# Nu_Multi.net
KiCad netlist of a schematic drawn in EAGLE
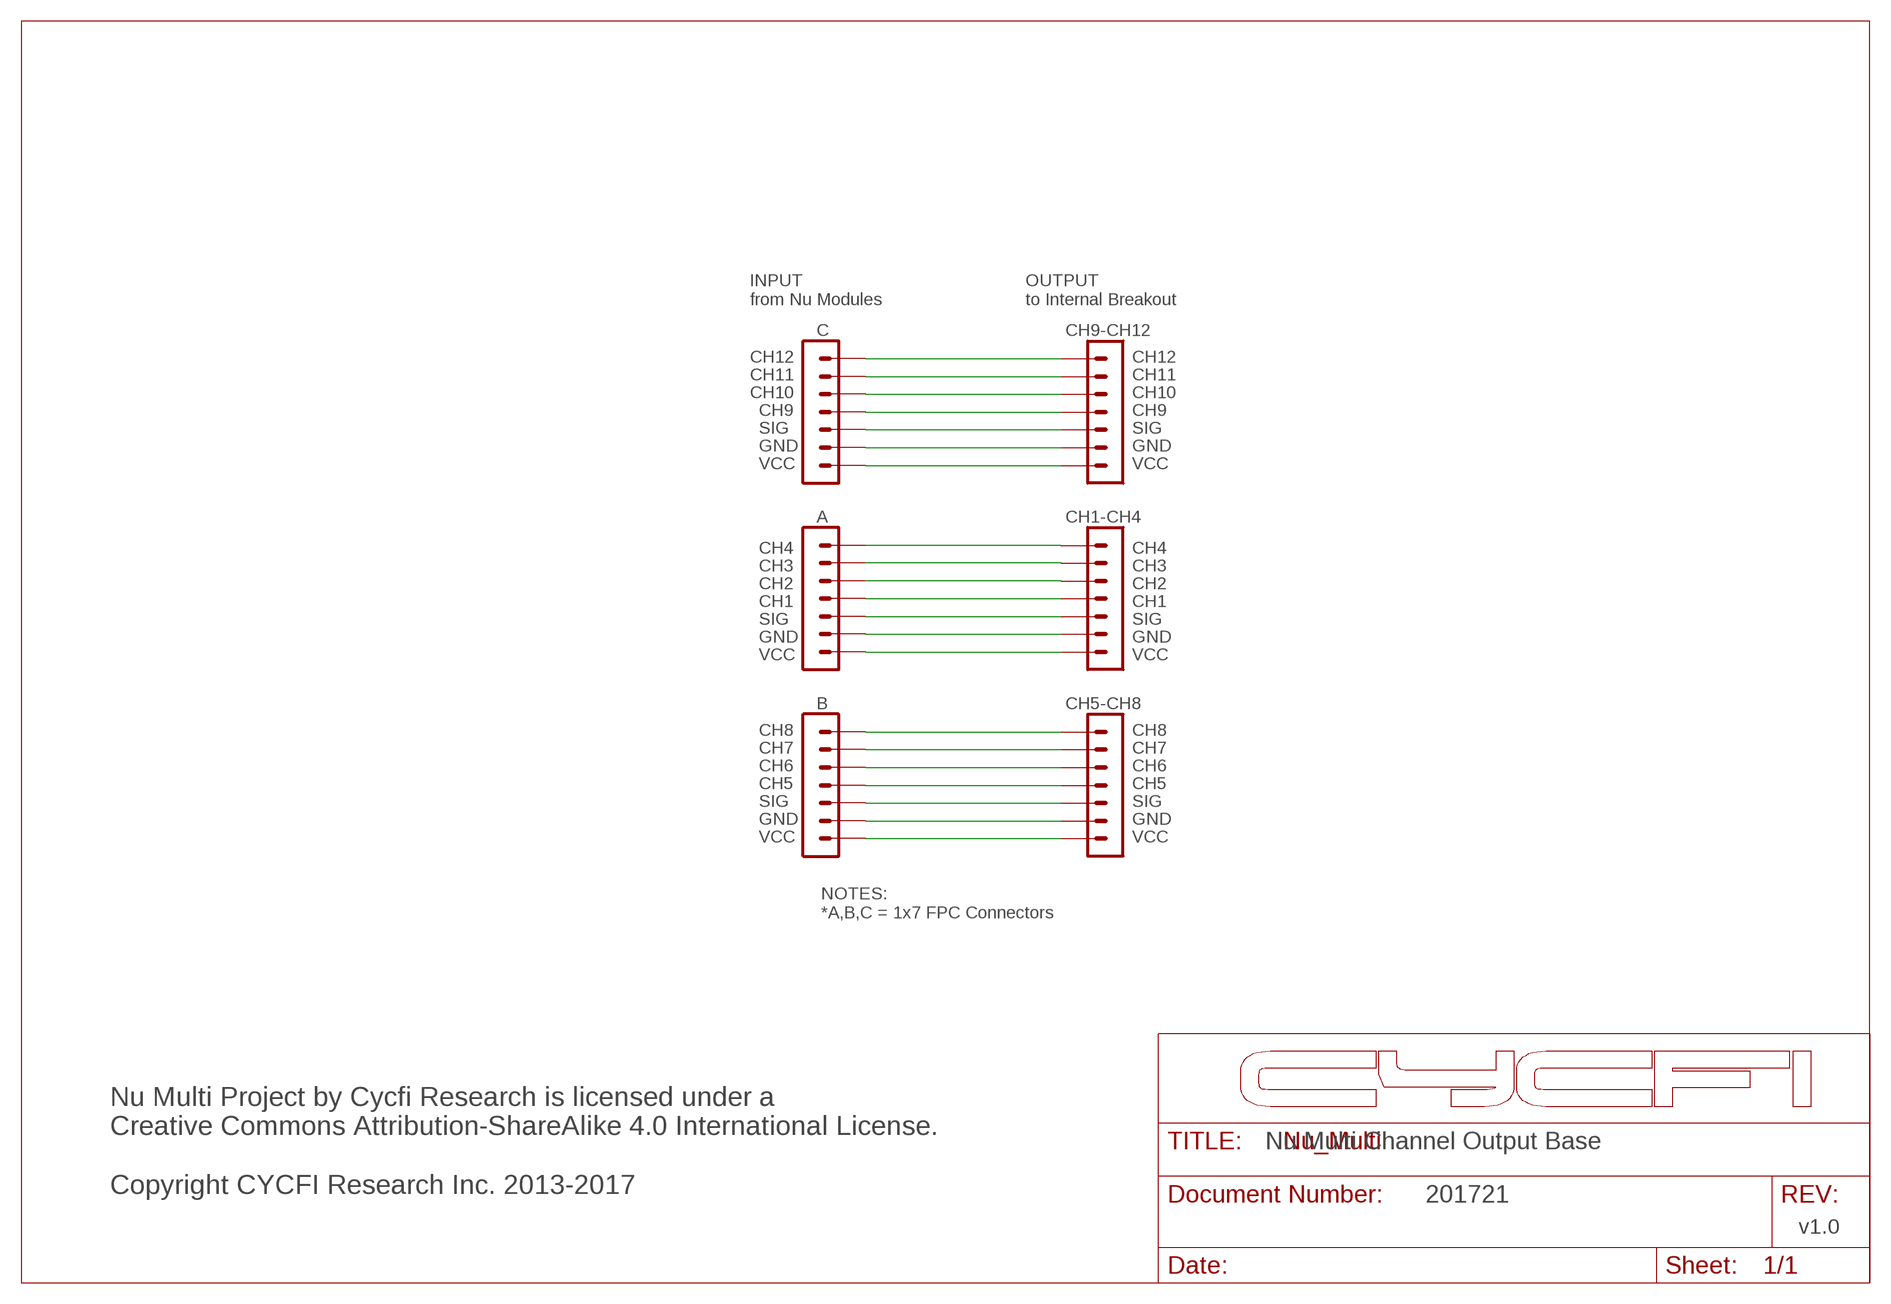
[diagram p0: schematic, sheet 1]

(export (version "E")
  (design (tool "Eeschema 10.0.6"))
  (components
    (comp (ref "H1")
      (value "7P_ZIF_59453-071110EDHLF")
      (footprint "eagle-import:7P_ZIF_59453-071110EDHLF")
      (libsource (lib "eagle-import") (part "7P_ZIF_59453-071110EDHLF"))
    )
    (comp (ref "H2")
      (value "7P_ZIF_59453-071110EDHLF")
      (footprint "eagle-import:7P_ZIF_59453-071110EDHLF")
      (libsource (lib "eagle-import") (part "7P_ZIF_59453-071110EDHLF"))
    )
    (comp (ref "H3")
      (value "7P_ZIF_59453-071110EDHLF")
      (footprint "eagle-import:7P_ZIF_59453-071110EDHLF")
      (libsource (lib "eagle-import") (part "7P_ZIF_59453-071110EDHLF"))
    )
    (comp (ref "H4")
      (value "7P_ZIF_59453-071110EDHLF")
      (footprint "eagle-import:7P_ZIF_59453-071110EDHLF")
      (libsource (lib "eagle-import") (part "7P_ZIF_59453-071110EDHLF"))
    )
    (comp (ref "H5")
      (value "7P_ZIF_59453-071110EDHLF")
      (footprint "eagle-import:7P_ZIF_59453-071110EDHLF")
      (libsource (lib "eagle-import") (part "7P_ZIF_59453-071110EDHLF"))
    )
    (comp (ref "H6")
      (value "7P_ZIF_59453-071110EDHLF")
      (footprint "eagle-import:7P_ZIF_59453-071110EDHLF")
      (libsource (lib "eagle-import") (part "7P_ZIF_59453-071110EDHLF"))
    )
  )
  (nets
    (net (code "1") (name "/GND") (class "Default")
      (node (ref "H1") (pin "P$6") (pinfunction "6_P$6") (pintype "passive"))
      (node (ref "H2") (pin "P$6") (pinfunction "6_P$6") (pintype "passive"))
      (node (ref "H3") (pin "P$6") (pinfunction "6_P$6") (pintype "passive"))
      (node (ref "H4") (pin "P$6") (pinfunction "6_P$6") (pintype "passive"))
      (node (ref "H5") (pin "P$6") (pinfunction "6_P$6") (pintype "passive"))
      (node (ref "H6") (pin "P$6") (pinfunction "6_P$6") (pintype "passive"))
    )
    (net (code "2") (name "Net-(H1-1)") (class "Default")
      (node (ref "H1") (pin "P$1") (pinfunction "1_P$1") (pintype "passive"))
      (node (ref "H3") (pin "P$1") (pinfunction "1_P$1") (pintype "passive"))
    )
    (net (code "3") (name "Net-(H1-2)") (class "Default")
      (node (ref "H1") (pin "P$2") (pinfunction "2_P$2") (pintype "passive"))
      (node (ref "H3") (pin "P$2") (pinfunction "2_P$2") (pintype "passive"))
    )
    (net (code "4") (name "Net-(H1-3)") (class "Default")
      (node (ref "H1") (pin "P$3") (pinfunction "3_P$3") (pintype "passive"))
      (node (ref "H3") (pin "P$3") (pinfunction "3_P$3") (pintype "passive"))
    )
    (net (code "5") (name "Net-(H1-4)") (class "Default")
      (node (ref "H1") (pin "P$4") (pinfunction "4_P$4") (pintype "passive"))
      (node (ref "H3") (pin "P$4") (pinfunction "4_P$4") (pintype "passive"))
    )
    (net (code "6") (name "Net-(H1-5)") (class "Default")
      (node (ref "H1") (pin "P$5") (pinfunction "5_P$5") (pintype "passive"))
      (node (ref "H3") (pin "P$5") (pinfunction "5_P$5") (pintype "passive"))
    )
    (net (code "7") (name "Net-(H1-7)") (class "Default")
      (node (ref "H1") (pin "P$7") (pinfunction "7_P$7") (pintype "passive"))
      (node (ref "H3") (pin "P$7") (pinfunction "7_P$7") (pintype "passive"))
    )
    (net (code "8") (name "Net-(H2-1)") (class "Default")
      (node (ref "H2") (pin "P$1") (pinfunction "1_P$1") (pintype "passive"))
      (node (ref "H4") (pin "P$1") (pinfunction "1_P$1") (pintype "passive"))
    )
    (net (code "9") (name "Net-(H2-2)") (class "Default")
      (node (ref "H2") (pin "P$2") (pinfunction "2_P$2") (pintype "passive"))
      (node (ref "H4") (pin "P$2") (pinfunction "2_P$2") (pintype "passive"))
    )
    (net (code "10") (name "Net-(H2-3)") (class "Default")
      (node (ref "H2") (pin "P$3") (pinfunction "3_P$3") (pintype "passive"))
      (node (ref "H4") (pin "P$3") (pinfunction "3_P$3") (pintype "passive"))
    )
    (net (code "11") (name "Net-(H2-4)") (class "Default")
      (node (ref "H2") (pin "P$4") (pinfunction "4_P$4") (pintype "passive"))
      (node (ref "H4") (pin "P$4") (pinfunction "4_P$4") (pintype "passive"))
    )
    (net (code "12") (name "Net-(H2-5)") (class "Default")
      (node (ref "H2") (pin "P$5") (pinfunction "5_P$5") (pintype "passive"))
      (node (ref "H4") (pin "P$5") (pinfunction "5_P$5") (pintype "passive"))
    )
    (net (code "13") (name "Net-(H2-7)") (class "Default")
      (node (ref "H2") (pin "P$7") (pinfunction "7_P$7") (pintype "passive"))
      (node (ref "H4") (pin "P$7") (pinfunction "7_P$7") (pintype "passive"))
    )
    (net (code "14") (name "Net-(H5-1)") (class "Default")
      (node (ref "H5") (pin "P$1") (pinfunction "1_P$1") (pintype "passive"))
      (node (ref "H6") (pin "P$1") (pinfunction "1_P$1") (pintype "passive"))
    )
    (net (code "15") (name "Net-(H5-2)") (class "Default")
      (node (ref "H5") (pin "P$2") (pinfunction "2_P$2") (pintype "passive"))
      (node (ref "H6") (pin "P$2") (pinfunction "2_P$2") (pintype "passive"))
    )
    (net (code "16") (name "Net-(H5-3)") (class "Default")
      (node (ref "H5") (pin "P$3") (pinfunction "3_P$3") (pintype "passive"))
      (node (ref "H6") (pin "P$3") (pinfunction "3_P$3") (pintype "passive"))
    )
    (net (code "17") (name "Net-(H5-4)") (class "Default")
      (node (ref "H5") (pin "P$4") (pinfunction "4_P$4") (pintype "passive"))
      (node (ref "H6") (pin "P$4") (pinfunction "4_P$4") (pintype "passive"))
    )
    (net (code "18") (name "Net-(H5-5)") (class "Default")
      (node (ref "H5") (pin "P$5") (pinfunction "5_P$5") (pintype "passive"))
      (node (ref "H6") (pin "P$5") (pinfunction "5_P$5") (pintype "passive"))
    )
    (net (code "19") (name "Net-(H5-7)") (class "Default")
      (node (ref "H5") (pin "P$7") (pinfunction "7_P$7") (pintype "passive"))
      (node (ref "H6") (pin "P$7") (pinfunction "7_P$7") (pintype "passive"))
    )
  )
)
